# CET_4_27_22.net
KiCad netlist of a schematic drawn in EAGLE
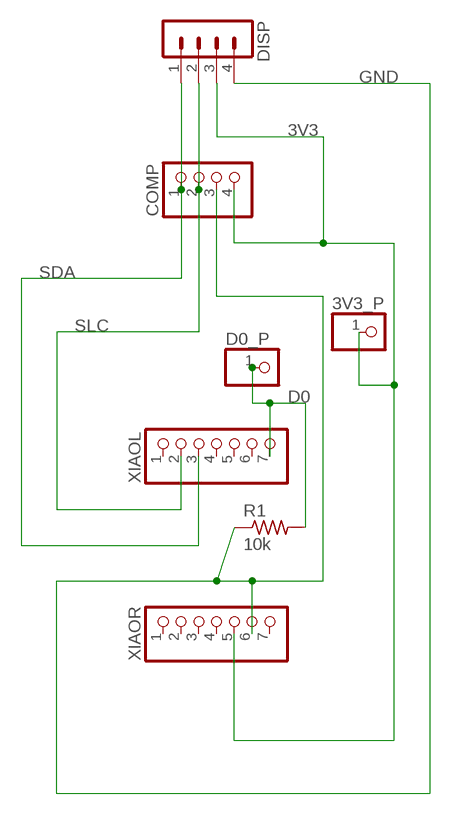
[diagram p0: schematic, sheet 1]

(export (version "E")
  (design (tool "Eeschema 10.0.6"))
  (components
    (comp (ref "3V3_P")
      (value "PINHD-1X1")
      (footprint "eagle-import:1X01")
      (libsource (lib "eagle-import") (part "PINHD-1X1"))
    )
    (comp (ref "COMP")
      (value "PINHD-1X4/90")
      (footprint "eagle-import:1X04_90")
      (libsource (lib "eagle-import") (part "PINHD-1X4/90"))
    )
    (comp (ref "D0_P")
      (value "PINHD-1X1")
      (footprint "eagle-import:1X01")
      (libsource (lib "eagle-import") (part "PINHD-1X1"))
    )
    (comp (ref "DISP")
      (value "MA04-1")
      (footprint "eagle-import:MA04-1")
      (libsource (lib "eagle-import") (part "MA04-1"))
    )
    (comp (ref "R1")
      (value "10k")
      (footprint "eagle-import:0204_7")
      (libsource (lib "eagle-import") (part "R-US_0204/7"))
    )
    (comp (ref "XIAOL")
      (value "PINHD-1X7")
      (footprint "eagle-import:1X07")
      (libsource (lib "eagle-import") (part "PINHD-1X7"))
    )
    (comp (ref "XIAOR")
      (value "PINHD-1X7")
      (footprint "eagle-import:1X07")
      (libsource (lib "eagle-import") (part "PINHD-1X7"))
    )
  )
  (nets
    (net (code "1") (name "/3V3") (class "Default")
      (node (ref "3V3_P") (pin "1") (pinfunction "1_1") (pintype "passive"))
      (node (ref "COMP") (pin "4") (pinfunction "4_4") (pintype "passive"))
      (node (ref "DISP") (pin "3") (pinfunction "3_3") (pintype "passive"))
      (node (ref "XIAOR") (pin "5") (pinfunction "5_5") (pintype "passive"))
    )
    (net (code "2") (name "/D0") (class "Default")
      (node (ref "D0_P") (pin "1") (pinfunction "1_1") (pintype "passive"))
      (node (ref "R1") (pin "2") (pinfunction "2_2") (pintype "passive"))
      (node (ref "XIAOL") (pin "7") (pinfunction "7_7") (pintype "passive"))
    )
    (net (code "3") (name "/GND") (class "Default")
      (node (ref "COMP") (pin "3") (pinfunction "3_3") (pintype "passive"))
      (node (ref "DISP") (pin "4") (pinfunction "4_4") (pintype "passive"))
      (node (ref "R1") (pin "1") (pinfunction "1_1") (pintype "passive"))
      (node (ref "XIAOR") (pin "6") (pinfunction "6_6") (pintype "passive"))
    )
    (net (code "4") (name "/SDA") (class "Default")
      (node (ref "COMP") (pin "1") (pinfunction "1_1") (pintype "passive"))
      (node (ref "DISP") (pin "1") (pinfunction "1_1") (pintype "passive"))
      (node (ref "XIAOL") (pin "3") (pinfunction "3_3") (pintype "passive"))
    )
    (net (code "5") (name "/SLC") (class "Default")
      (node (ref "COMP") (pin "2") (pinfunction "2_2") (pintype "passive"))
      (node (ref "DISP") (pin "2") (pinfunction "2_2") (pintype "passive"))
      (node (ref "XIAOL") (pin "2") (pinfunction "2_2") (pintype "passive"))
    )
    (net (code "6") (name "unconnected-(XIAOL-Pad1)") (class "Default")
      (node (ref "XIAOL") (pin "1") (pinfunction "1_1") (pintype "passive"))
    )
    (net (code "7") (name "unconnected-(XIAOL-Pad4)") (class "Default")
      (node (ref "XIAOL") (pin "4") (pinfunction "4_4") (pintype "passive"))
    )
    (net (code "8") (name "unconnected-(XIAOL-Pad5)") (class "Default")
      (node (ref "XIAOL") (pin "5") (pinfunction "5_5") (pintype "passive"))
    )
    (net (code "9") (name "unconnected-(XIAOL-Pad6)") (class "Default")
      (node (ref "XIAOL") (pin "6") (pinfunction "6_6") (pintype "passive"))
    )
    (net (code "10") (name "unconnected-(XIAOR-Pad1)") (class "Default")
      (node (ref "XIAOR") (pin "1") (pinfunction "1_1") (pintype "passive"))
    )
    (net (code "11") (name "unconnected-(XIAOR-Pad2)") (class "Default")
      (node (ref "XIAOR") (pin "2") (pinfunction "2_2") (pintype "passive"))
    )
    (net (code "12") (name "unconnected-(XIAOR-Pad3)") (class "Default")
      (node (ref "XIAOR") (pin "3") (pinfunction "3_3") (pintype "passive"))
    )
    (net (code "13") (name "unconnected-(XIAOR-Pad4)") (class "Default")
      (node (ref "XIAOR") (pin "4") (pinfunction "4_4") (pintype "passive"))
    )
    (net (code "14") (name "unconnected-(XIAOR-Pad7)") (class "Default")
      (node (ref "XIAOR") (pin "7") (pinfunction "7_7") (pintype "passive"))
    )
  )
)
